# GPIO_BOARD.net
KiCad netlist of a schematic drawn in EAGLE
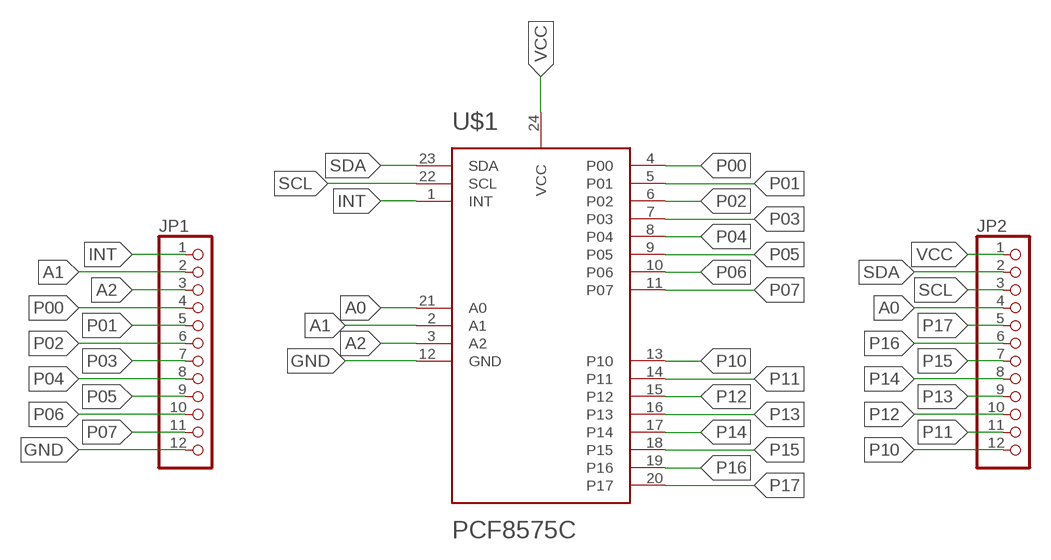
[diagram p0: schematic, sheet 1]

(export (version "E")
  (design (tool "Eeschema 10.0.6"))
  (components
    (comp (ref "JP1")
      (value "PINHD-1X12")
      (footprint "eagle-import:1X12")
      (libsource (lib "eagle-import") (part "PINHD-1X12"))
    )
    (comp (ref "JP2")
      (value "PINHD-1X12")
      (footprint "eagle-import:1X12")
      (libsource (lib "eagle-import") (part "PINHD-1X12"))
    )
    (comp (ref "U$1")
      (value "PCF8575C")
      (footprint "eagle-import:PCF8575C")
      (libsource (lib "eagle-import") (part "PCF8575C"))
    )
  )
  (nets
    (net (code "1") (name "A0") (class "Default")
      (node (ref "JP2") (pin "4") (pinfunction "4_4") (pintype "passive"))
      (node (ref "U$1") (pin "21") (pinfunction "A0_21") (pintype "bidirectional"))
    )
    (net (code "2") (name "A1") (class "Default")
      (node (ref "JP1") (pin "2") (pinfunction "2_2") (pintype "passive"))
      (node (ref "U$1") (pin "2") (pinfunction "A1_2") (pintype "bidirectional"))
    )
    (net (code "3") (name "A2") (class "Default")
      (node (ref "JP1") (pin "3") (pinfunction "3_3") (pintype "passive"))
      (node (ref "U$1") (pin "3") (pinfunction "A2_3") (pintype "bidirectional"))
    )
    (net (code "4") (name "GND") (class "Default")
      (node (ref "JP1") (pin "12") (pinfunction "12_12") (pintype "passive"))
      (node (ref "U$1") (pin "12") (pinfunction "GND_12") (pintype "bidirectional"))
    )
    (net (code "5") (name "INT") (class "Default")
      (node (ref "JP1") (pin "1") (pinfunction "1_1") (pintype "passive"))
      (node (ref "U$1") (pin "1") (pinfunction "INT_1") (pintype "bidirectional"))
    )
    (net (code "6") (name "P00") (class "Default")
      (node (ref "JP1") (pin "4") (pinfunction "4_4") (pintype "passive"))
      (node (ref "U$1") (pin "4") (pinfunction "P00_4") (pintype "bidirectional"))
    )
    (net (code "7") (name "P01") (class "Default")
      (node (ref "JP1") (pin "5") (pinfunction "5_5") (pintype "passive"))
      (node (ref "U$1") (pin "5") (pinfunction "P01_5") (pintype "bidirectional"))
    )
    (net (code "8") (name "P02") (class "Default")
      (node (ref "JP1") (pin "6") (pinfunction "6_6") (pintype "passive"))
      (node (ref "U$1") (pin "6") (pinfunction "P02_6") (pintype "bidirectional"))
    )
    (net (code "9") (name "P03") (class "Default")
      (node (ref "JP1") (pin "7") (pinfunction "7_7") (pintype "passive"))
      (node (ref "U$1") (pin "7") (pinfunction "P03_7") (pintype "bidirectional"))
    )
    (net (code "10") (name "P04") (class "Default")
      (node (ref "JP1") (pin "8") (pinfunction "8_8") (pintype "passive"))
      (node (ref "U$1") (pin "8") (pinfunction "P04_8") (pintype "bidirectional"))
    )
    (net (code "11") (name "P05") (class "Default")
      (node (ref "JP1") (pin "9") (pinfunction "9_9") (pintype "passive"))
      (node (ref "U$1") (pin "9") (pinfunction "P05_9") (pintype "bidirectional"))
    )
    (net (code "12") (name "P06") (class "Default")
      (node (ref "JP1") (pin "10") (pinfunction "10_10") (pintype "passive"))
      (node (ref "U$1") (pin "10") (pinfunction "P06_10") (pintype "bidirectional"))
    )
    (net (code "13") (name "P07") (class "Default")
      (node (ref "JP1") (pin "11") (pinfunction "11_11") (pintype "passive"))
      (node (ref "U$1") (pin "11") (pinfunction "P07_11") (pintype "bidirectional"))
    )
    (net (code "14") (name "P10") (class "Default")
      (node (ref "JP2") (pin "12") (pinfunction "12_12") (pintype "passive"))
      (node (ref "U$1") (pin "13") (pinfunction "P10_13") (pintype "bidirectional"))
    )
    (net (code "15") (name "P11") (class "Default")
      (node (ref "JP2") (pin "11") (pinfunction "11_11") (pintype "passive"))
      (node (ref "U$1") (pin "14") (pinfunction "P11_14") (pintype "bidirectional"))
    )
    (net (code "16") (name "P12") (class "Default")
      (node (ref "JP2") (pin "10") (pinfunction "10_10") (pintype "passive"))
      (node (ref "U$1") (pin "15") (pinfunction "P12_15") (pintype "bidirectional"))
    )
    (net (code "17") (name "P13") (class "Default")
      (node (ref "JP2") (pin "9") (pinfunction "9_9") (pintype "passive"))
      (node (ref "U$1") (pin "16") (pinfunction "P13_16") (pintype "bidirectional"))
    )
    (net (code "18") (name "P14") (class "Default")
      (node (ref "JP2") (pin "8") (pinfunction "8_8") (pintype "passive"))
      (node (ref "U$1") (pin "17") (pinfunction "P14_17") (pintype "bidirectional"))
    )
    (net (code "19") (name "P15") (class "Default")
      (node (ref "JP2") (pin "7") (pinfunction "7_7") (pintype "passive"))
      (node (ref "U$1") (pin "18") (pinfunction "P15_18") (pintype "bidirectional"))
    )
    (net (code "20") (name "P16") (class "Default")
      (node (ref "JP2") (pin "6") (pinfunction "6_6") (pintype "passive"))
      (node (ref "U$1") (pin "19") (pinfunction "P16_19") (pintype "bidirectional"))
    )
    (net (code "21") (name "P17") (class "Default")
      (node (ref "JP2") (pin "5") (pinfunction "5_5") (pintype "passive"))
      (node (ref "U$1") (pin "20") (pinfunction "P17_20") (pintype "bidirectional"))
    )
    (net (code "22") (name "SCL") (class "Default")
      (node (ref "JP2") (pin "3") (pinfunction "3_3") (pintype "passive"))
      (node (ref "U$1") (pin "22") (pinfunction "SCL_22") (pintype "bidirectional"))
    )
    (net (code "23") (name "SDA") (class "Default")
      (node (ref "JP2") (pin "2") (pinfunction "2_2") (pintype "passive"))
      (node (ref "U$1") (pin "23") (pinfunction "SDA_23") (pintype "bidirectional"))
    )
    (net (code "24") (name "VCC") (class "Default")
      (node (ref "JP2") (pin "1") (pinfunction "1_1") (pintype "passive"))
      (node (ref "U$1") (pin "24") (pinfunction "VCC_24") (pintype "bidirectional"))
    )
  )
)
